# Center_Console.net
KiCad netlist of a schematic drawn in Altium Designer
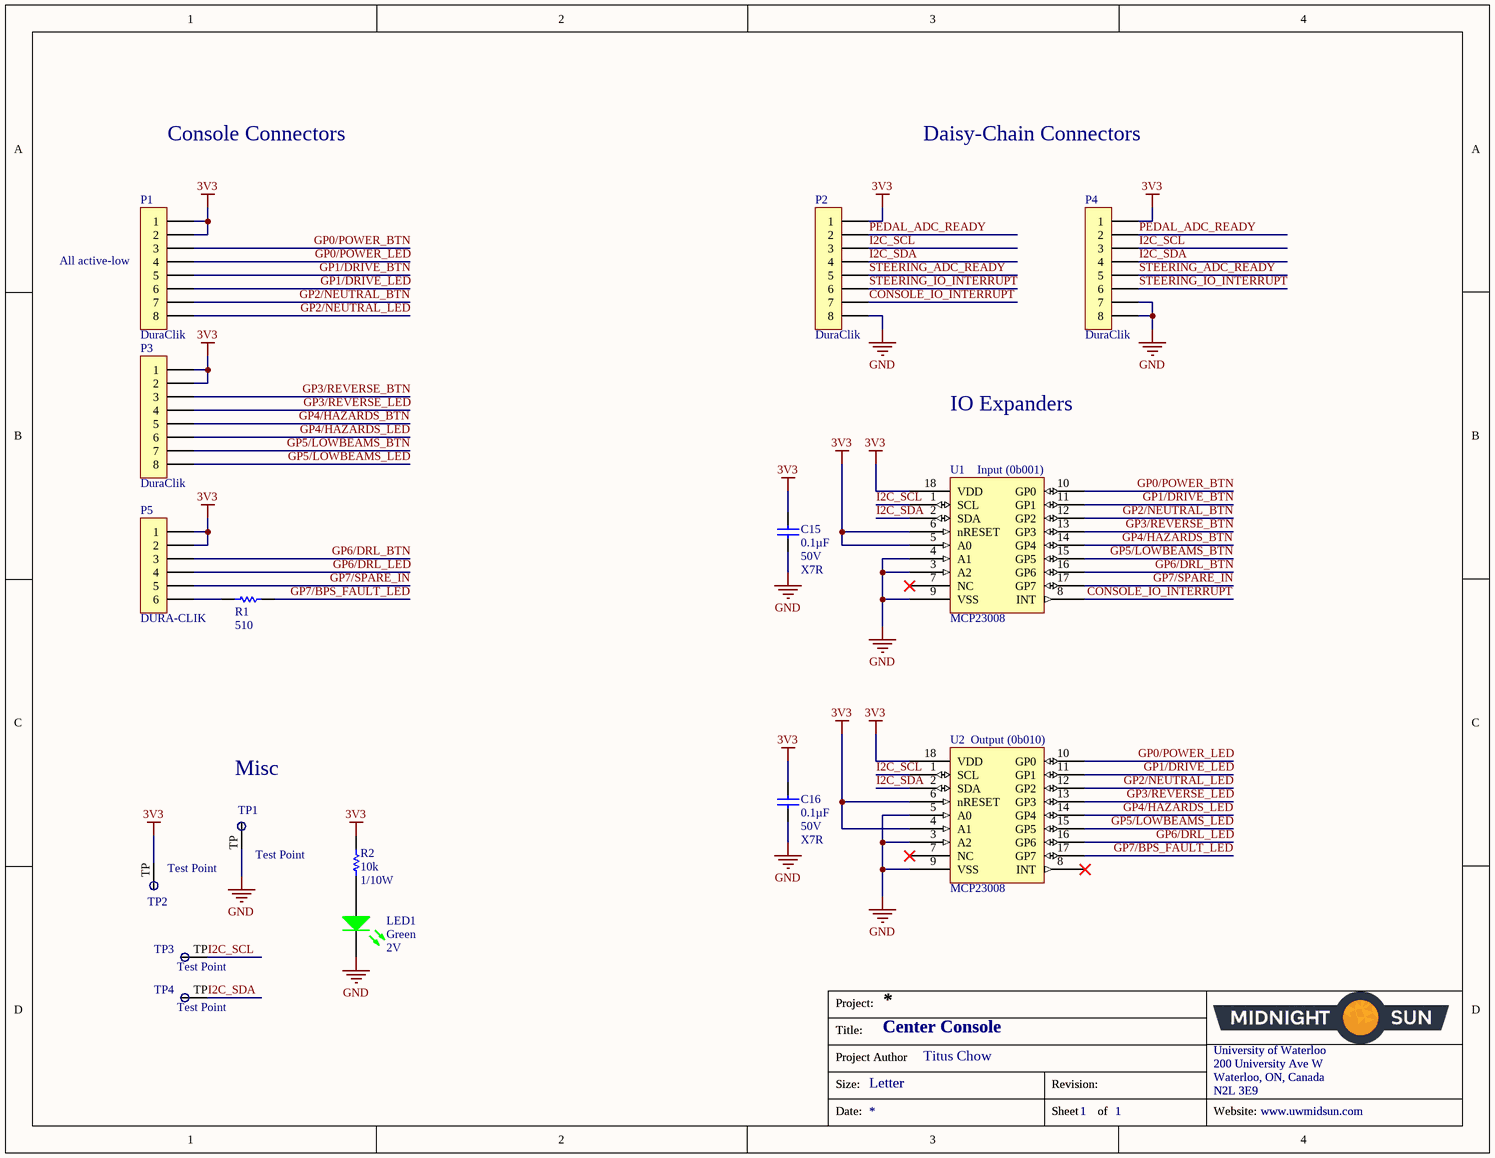
[diagram p0: Center Console.SchDoc]

(export (version "E")
  (design (tool "Eeschema 10.0.6"))
  (components
    (comp (ref "C15")
      (value "CAP CER 0.1UF 50V 10% X7R 0603")
      (footprint "CAP, 0603")
      (description "0.10µF ±10% 50V Ceramic Capacitor X7R 0603 (1608 Metric)")
      (fields
        (field (name "TOLERANCE") "±10%")
        (field (name "CAPACITANCE") "0.1µF")
        (field (name "VOLTAGE") "50V")
        (field (name "TEMPERATURE COEFFICIENT") "X7R")
      )
      (libsource (lib "Schematic Diagrams") (part "CAP CER 0.1UF 50V 10% X7R 0603"))
    )
    (comp (ref "C16")
      (value "CAP CER 0.1UF 50V 10% X7R 0603")
      (footprint "CAP, 0603")
      (description "0.10µF ±10% 50V Ceramic Capacitor X7R 0603 (1608 Metric)")
      (fields
        (field (name "TOLERANCE") "±10%")
        (field (name "CAPACITANCE") "0.1µF")
        (field (name "VOLTAGE") "50V")
        (field (name "TEMPERATURE COEFFICIENT") "X7R")
      )
      (libsource (lib "Schematic Diagrams") (part "CAP CER 0.1UF 50V 10% X7R 0603"))
    )
    (comp (ref "LED1")
      (value "LED GREEN CLEAR 2V 0603")
      (footprint "LED_0603")
      (description "Green 572nm LED Indication - Discrete 2V 0603 (1608 Metric)")
      (fields
        (field (name "MANUFACTURER") "Wurth Electronics Inc.")
        (field (name "MANUFACTURER PART NUMBER") "150060VS75000")
        (field (name "COLOR") "Green")
        (field (name "VOLTAGE - FORWARD (VF) (TYP)") "2V")
      )
      (libsource (lib "Schematic Diagrams") (part "LED GREEN CLEAR 2V 0603"))
    )
    (comp (ref "P1")
      (value "CONN 8POS DURA-CLIK 0.079\"")
      (footprint "CONN, 8POS Dura-Clik")
      (description "8 Positions Header Connector 0.079\" (2.00mm) Surface Mount Tin")
      (fields (field (name "SERIES") "DuraClik"))
      (libsource (lib "Schematic Diagrams") (part "CONN 8POS DURA-CLIK 0.079{dblquote}"))
    )
    (comp (ref "P2")
      (value "CONN 8POS DURA-CLIK 0.079\"")
      (footprint "CONN, 8POS Dura-Clik")
      (description "8 Positions Header Connector 0.079\" (2.00mm) Surface Mount Tin")
      (fields (field (name "SERIES") "DuraClik"))
      (libsource (lib "Schematic Diagrams") (part "CONN 8POS DURA-CLIK 0.079{dblquote}"))
    )
    (comp (ref "P3")
      (value "CONN 8POS DURA-CLIK 0.079\"")
      (footprint "CONN, 8POS Dura-Clik")
      (description "8 Positions Header Connector 0.079\" (2.00mm) Surface Mount Tin")
      (fields (field (name "SERIES") "DuraClik"))
      (libsource (lib "Schematic Diagrams") (part "CONN 8POS DURA-CLIK 0.079{dblquote}"))
    )
    (comp (ref "P4")
      (value "CONN 8POS DURA-CLIK 0.079\"")
      (footprint "CONN, 8POS Dura-Clik")
      (description "8 Positions Header Connector 0.079\" (2.00mm) Surface Mount Tin")
      (fields (field (name "SERIES") "DuraClik"))
      (libsource (lib "Schematic Diagrams") (part "CONN 8POS DURA-CLIK 0.079{dblquote}"))
    )
    (comp (ref "P5")
      (value "DURA-CLIK")
      (footprint "CONN, 6POS DURA-CLIK VERT")
      (description "6 Positions Header, Shrouded Connector 0.079\" (2.00mm) Surface Mount, Vertical Tin")
      (fields (field (name "MANUFACTURER") "Molex") (field (name "MANUFACTURER PART NUMBER") "5600200820"))
      (libsource (lib "Schematic Diagrams") (part "CONN 6POS DURA-CLIK 0.079{dblquote}"))
    )
    (comp (ref "R1")
      (value "RES 510 OHM 5% 1/10W 0603")
      (footprint "RES, 0603")
      (description "RES SMD 510 OHM 5% 1/10W 0603")
      (fields
        (field (name "TOLERANCE") "±5%")
        (field (name "RESISTANCE") "510")
        (field (name "POWER") "1/10W")
      )
      (libsource (lib "Schematic Diagrams") (part "RES 510 OHM 5% 1/10W 0603"))
    )
    (comp (ref "R2")
      (value "RES 10K OHM 1% 1/10W 0603")
      (footprint "RES, 0603")
      (description "RES SMD 10K OHM 1% 1/10W 0603")
      (fields
        (field (name "TOLERANCE") "±1%")
        (field (name "RESISTANCE") "10k")
        (field (name "POWER") "1/10W")
      )
      (libsource (lib "Schematic Diagrams") (part "RES 10K OHM 1% 1/10W 0603"))
    )
    (comp (ref "TP1")
      (value "Test Point")
      (footprint "Test Point")
      (libsource (lib "Schematic Diagrams") (part "Test Point"))
    )
    (comp (ref "TP2")
      (value "Test Point")
      (footprint "Test Point")
      (libsource (lib "Schematic Diagrams") (part "Test Point"))
    )
    (comp (ref "TP3")
      (value "Test Point")
      (footprint "Test Point")
      (libsource (lib "Schematic Diagrams") (part "Test Point"))
    )
    (comp (ref "TP4")
      (value "Test Point")
      (footprint "Test Point")
      (libsource (lib "Schematic Diagrams") (part "Test Point"))
    )
    (comp (ref "U1")
      (value "MCP23008")
      (footprint "IC 18SOIC")
      (description "MCP23008 I/O Expander 8B+1Int 18P SOIC")
      (fields
        (field (name "MANUFACTURER") "Microchip Technology")
        (field (name "MANUFACTURER PART NUMBER") "MCP23008T-E/SO")
      )
      (libsource (lib "Schematic Diagrams") (part "IC I/O EXPANDER I2C 8B 18SOIC"))
    )
    (comp (ref "U2")
      (value "MCP23008")
      (footprint "IC 18SOIC")
      (description "MCP23008 I/O Expander 8B+1Int 18P SOIC")
      (fields
        (field (name "MANUFACTURER") "Microchip Technology")
        (field (name "MANUFACTURER PART NUMBER") "MCP23008T-E/SO")
      )
      (libsource (lib "Schematic Diagrams") (part "IC I/O EXPANDER I2C 8B 18SOIC"))
    )
  )
  (nets
    (net (code "1") (name "/CONSOLE_IO_INTERRUPT") (class "Default")
      (node (ref "P2") (pin "7") (pinfunction "7_7") (pintype "passive"))
      (node (ref "U1") (pin "8") (pinfunction "INT_8") (pintype "output"))
    )
    (net (code "2") (name "/GP0{slash}POWER_BTN") (class "Default")
      (node (ref "P1") (pin "3") (pinfunction "3_3") (pintype "passive"))
      (node (ref "U1") (pin "10") (pinfunction "GP0_10") (pintype "bidirectional"))
    )
    (net (code "3") (name "/GP0{slash}POWER_LED") (class "Default")
      (node (ref "P1") (pin "4") (pinfunction "4_4") (pintype "passive"))
      (node (ref "U2") (pin "10") (pinfunction "GP0_10") (pintype "bidirectional"))
    )
    (net (code "4") (name "/GP1{slash}DRIVE_BTN") (class "Default")
      (node (ref "P1") (pin "5") (pinfunction "5_5") (pintype "passive"))
      (node (ref "U1") (pin "11") (pinfunction "GP1_11") (pintype "bidirectional"))
    )
    (net (code "5") (name "/GP1{slash}DRIVE_LED") (class "Default")
      (node (ref "P1") (pin "6") (pinfunction "6_6") (pintype "passive"))
      (node (ref "U2") (pin "11") (pinfunction "GP1_11") (pintype "bidirectional"))
    )
    (net (code "6") (name "/GP2{slash}NEUTRAL_BTN") (class "Default")
      (node (ref "P1") (pin "7") (pinfunction "7_7") (pintype "passive"))
      (node (ref "U1") (pin "12") (pinfunction "GP2_12") (pintype "bidirectional"))
    )
    (net (code "7") (name "/GP2{slash}NEUTRAL_LED") (class "Default")
      (node (ref "P1") (pin "8") (pinfunction "8_8") (pintype "passive"))
      (node (ref "U2") (pin "12") (pinfunction "GP2_12") (pintype "bidirectional"))
    )
    (net (code "8") (name "/GP3{slash}REVERSE_BTN") (class "Default")
      (node (ref "P3") (pin "3") (pinfunction "3_3") (pintype "passive"))
      (node (ref "U1") (pin "13") (pinfunction "GP3_13") (pintype "bidirectional"))
    )
    (net (code "9") (name "/GP3{slash}REVERSE_LED") (class "Default")
      (node (ref "P3") (pin "4") (pinfunction "4_4") (pintype "passive"))
      (node (ref "U2") (pin "13") (pinfunction "GP3_13") (pintype "bidirectional"))
    )
    (net (code "10") (name "/GP4{slash}HAZARDS_BTN") (class "Default")
      (node (ref "P3") (pin "5") (pinfunction "5_5") (pintype "passive"))
      (node (ref "U1") (pin "14") (pinfunction "GP4_14") (pintype "bidirectional"))
    )
    (net (code "11") (name "/GP4{slash}HAZARDS_LED") (class "Default")
      (node (ref "P3") (pin "6") (pinfunction "6_6") (pintype "passive"))
      (node (ref "U2") (pin "14") (pinfunction "GP4_14") (pintype "bidirectional"))
    )
    (net (code "12") (name "/GP5{slash}LOWBEAMS_BTN") (class "Default")
      (node (ref "P3") (pin "7") (pinfunction "7_7") (pintype "passive"))
      (node (ref "U1") (pin "15") (pinfunction "GP5_15") (pintype "bidirectional"))
    )
    (net (code "13") (name "/GP5{slash}LOWBEAMS_LED") (class "Default")
      (node (ref "P3") (pin "8") (pinfunction "8_8") (pintype "passive"))
      (node (ref "U2") (pin "15") (pinfunction "GP5_15") (pintype "bidirectional"))
    )
    (net (code "14") (name "/GP6{slash}DRL_BTN") (class "Default")
      (node (ref "P5") (pin "3") (pinfunction "3_3") (pintype "passive"))
      (node (ref "U1") (pin "16") (pinfunction "GP6_16") (pintype "bidirectional"))
    )
    (net (code "15") (name "/GP6{slash}DRL_LED") (class "Default")
      (node (ref "P5") (pin "4") (pinfunction "4_4") (pintype "passive"))
      (node (ref "U2") (pin "16") (pinfunction "GP6_16") (pintype "bidirectional"))
    )
    (net (code "16") (name "/GP7{slash}BPS_FAULT_LED") (class "Default")
      (node (ref "R1") (pin "2") (pinfunction "2_2") (pintype "passive"))
      (node (ref "U2") (pin "17") (pinfunction "GP7_17") (pintype "bidirectional"))
    )
    (net (code "17") (name "/GP7{slash}SPARE_IN") (class "Default")
      (node (ref "P5") (pin "5") (pinfunction "5_5") (pintype "passive"))
      (node (ref "U1") (pin "17") (pinfunction "GP7_17") (pintype "bidirectional"))
    )
    (net (code "18") (name "/I2C_SCL") (class "Default")
      (node (ref "P2") (pin "3") (pinfunction "3_3") (pintype "passive"))
      (node (ref "P4") (pin "3") (pinfunction "3_3") (pintype "passive"))
      (node (ref "TP3") (pin "TP") (pinfunction "1_TP") (pintype "passive"))
      (node (ref "U1") (pin "1") (pinfunction "SCL_1") (pintype "bidirectional"))
      (node (ref "U2") (pin "1") (pinfunction "SCL_1") (pintype "bidirectional"))
    )
    (net (code "19") (name "/I2C_SDA") (class "Default")
      (node (ref "P2") (pin "4") (pinfunction "4_4") (pintype "passive"))
      (node (ref "P4") (pin "4") (pinfunction "4_4") (pintype "passive"))
      (node (ref "TP4") (pin "TP") (pinfunction "1_TP") (pintype "passive"))
      (node (ref "U1") (pin "2") (pinfunction "SDA_2") (pintype "bidirectional"))
      (node (ref "U2") (pin "2") (pinfunction "SDA_2") (pintype "bidirectional"))
    )
    (net (code "20") (name "/PEDAL_ADC_READY") (class "Default")
      (node (ref "P2") (pin "2") (pinfunction "2_2") (pintype "passive"))
      (node (ref "P4") (pin "2") (pinfunction "2_2") (pintype "passive"))
    )
    (net (code "21") (name "/STEERING_ADC_READY") (class "Default")
      (node (ref "P2") (pin "5") (pinfunction "5_5") (pintype "passive"))
      (node (ref "P4") (pin "5") (pinfunction "5_5") (pintype "passive"))
    )
    (net (code "22") (name "/STEERING_IO_INTERRUPT") (class "Default")
      (node (ref "P2") (pin "6") (pinfunction "6_6") (pintype "passive"))
      (node (ref "P4") (pin "6") (pinfunction "6_6") (pintype "passive"))
    )
    (net (code "23") (name "3V3") (class "Default")
      (node (ref "C15") (pin "1") (pinfunction "1_1") (pintype "passive"))
      (node (ref "C16") (pin "1") (pinfunction "1_1") (pintype "passive"))
      (node (ref "P1") (pin "1") (pinfunction "1_1") (pintype "passive"))
      (node (ref "P1") (pin "2") (pinfunction "2_2") (pintype "passive"))
      (node (ref "P2") (pin "1") (pinfunction "1_1") (pintype "passive"))
      (node (ref "P3") (pin "1") (pinfunction "1_1") (pintype "passive"))
      (node (ref "P3") (pin "2") (pinfunction "2_2") (pintype "passive"))
      (node (ref "P4") (pin "1") (pinfunction "1_1") (pintype "passive"))
      (node (ref "P5") (pin "1") (pinfunction "1_1") (pintype "passive"))
      (node (ref "P5") (pin "2") (pinfunction "2_2") (pintype "passive"))
      (node (ref "R2") (pin "1") (pinfunction "1_1") (pintype "passive"))
      (node (ref "TP2") (pin "TP") (pinfunction "1_TP") (pintype "passive"))
      (node (ref "U1") (pin "18") (pinfunction "VDD_18") (pintype "power_in"))
      (node (ref "U1") (pin "5") (pinfunction "A0_5") (pintype "input"))
      (node (ref "U1") (pin "6") (pinfunction "nRESET_6") (pintype "input"))
      (node (ref "U2") (pin "18") (pinfunction "VDD_18") (pintype "power_in"))
      (node (ref "U2") (pin "4") (pinfunction "A1_4") (pintype "input"))
      (node (ref "U2") (pin "6") (pinfunction "nRESET_6") (pintype "input"))
    )
    (net (code "24") (name "GND") (class "Default")
      (node (ref "C15") (pin "2") (pinfunction "2_2") (pintype "passive"))
      (node (ref "C16") (pin "2") (pinfunction "2_2") (pintype "passive"))
      (node (ref "LED1") (pin "2") (pinfunction "K_2") (pintype "passive"))
      (node (ref "P2") (pin "8") (pinfunction "8_8") (pintype "passive"))
      (node (ref "P4") (pin "7") (pinfunction "7_7") (pintype "passive"))
      (node (ref "P4") (pin "8") (pinfunction "8_8") (pintype "passive"))
      (node (ref "TP1") (pin "TP") (pinfunction "1_TP") (pintype "passive"))
      (node (ref "U1") (pin "3") (pinfunction "A2_3") (pintype "input"))
      (node (ref "U1") (pin "4") (pinfunction "A1_4") (pintype "input"))
      (node (ref "U1") (pin "9") (pinfunction "VSS_9") (pintype "power_in"))
      (node (ref "U2") (pin "3") (pinfunction "A2_3") (pintype "input"))
      (node (ref "U2") (pin "5") (pinfunction "A0_5") (pintype "input"))
      (node (ref "U2") (pin "9") (pinfunction "VSS_9") (pintype "power_in"))
    )
    (net (code "25") (name "Net-(LED1-A)") (class "Default")
      (node (ref "LED1") (pin "1") (pinfunction "A_1") (pintype "passive"))
      (node (ref "R2") (pin "2") (pinfunction "2_2") (pintype "passive"))
    )
    (net (code "26") (name "Net-(P5-Pad6)") (class "Default")
      (node (ref "P5") (pin "6") (pinfunction "6_6") (pintype "passive"))
      (node (ref "R1") (pin "1") (pinfunction "1_1") (pintype "passive"))
    )
    (net (code "27") (name "unconnected-(U1-NC-Pad7)") (class "Default")
      (node (ref "U1") (pin "7") (pinfunction "NC_7") (pintype "passive+no_connect"))
    )
    (net (code "28") (name "unconnected-(U2-INT-Pad8)") (class "Default")
      (node (ref "U2") (pin "8") (pinfunction "INT_8") (pintype "output+no_connect"))
    )
    (net (code "29") (name "unconnected-(U2-NC-Pad7)") (class "Default")
      (node (ref "U2") (pin "7") (pinfunction "NC_7") (pintype "passive+no_connect"))
    )
  )
)
